# Sheet.net
KiCad netlist of a schematic drawn in Altium Designer
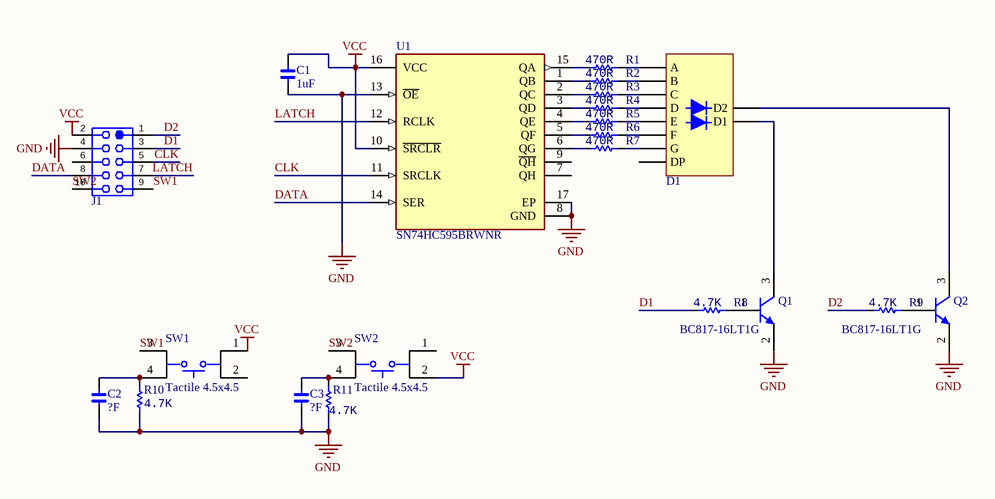
[diagram p0: Sheet.SchDoc]

(export (version "E")
  (design (tool "Eeschema 10.0.6"))
  (components
    (comp (ref "C1")
      (value "1uF")
      (footprint "C0603C-IPC_B")
      (description "0603 Multilayer Ceramic Capacitors MLCC - SMD/SMT ROHS")
      (libsource (lib "MAT_Component_Support") (part "Cap_0603"))
    )
    (comp (ref "C2")
      (value "?F")
      (footprint "C0603C-IPC_B")
      (description "0603 Multilayer Ceramic Capacitors MLCC - SMD/SMT ROHS")
      (libsource (lib "MAT_Component_Support") (part "Cap_0603"))
    )
    (comp (ref "C3")
      (value "?F")
      (footprint "C0603C-IPC_B")
      (description "0603 Multilayer Ceramic Capacitors MLCC - SMD/SMT ROHS")
      (libsource (lib "MAT_Component_Support") (part "Cap_0603"))
    )
    (comp (ref "D1")
      (value "7SEG_028_DUAL_CC")
      (footprint "7seg_2digit_028inch")
      (description "Common-Cathode (CC)")
      (libsource (lib "MAT_Component_Support") (part "2821AS"))
    )
    (comp (ref "J1")
      (value "HDRM_2x5_127_90")
      (footprint "HDRM_2x05J_90")
      (libsource (lib "MAT_Component_Support") (part "HDRM_2x5_127_90"))
    )
    (comp (ref "Q1")
      (value "BC817-16LT1G")
      (footprint "ONSC-SOT-23-3-318-08_V")
      (description "General Purpose Transistor, NPN Silicon, 3-Pin SOT-23, Pb-Free, Tape and Reel")
      (fields (field (name "MANUFACTURER") "On Semiconductor"))
      (libsource (lib "Altium Content Vault") (part "ONSC-NPN-B1E2C3-3"))
    )
    (comp (ref "Q2")
      (value "BC817-16LT1G")
      (footprint "ONSC-SOT-23-3-318-08_V")
      (description "General Purpose Transistor, NPN Silicon, 3-Pin SOT-23, Pb-Free, Tape and Reel")
      (fields (field (name "MANUFACTURER") "On Semiconductor"))
      (libsource (lib "Altium Content Vault") (part "ONSC-NPN-B1E2C3-3"))
    )
    (comp (ref "R1")
      (value "RC-0603")
      (footprint "RC0603-IPC_B")
      (description "±1% 0603 Chip Resistor - Surface Mount ROHS")
      (fields (field (name "TOLERANCE") "±1%") (field (name "RESISTANCE") "470R"))
      (libsource (lib "[MAT]_Resistors") (part "RC-0603"))
    )
    (comp (ref "R2")
      (value "RC-0603")
      (footprint "RC0603-IPC_B")
      (description "±1% 0603 Chip Resistor - Surface Mount ROHS")
      (fields (field (name "TOLERANCE") "±1%") (field (name "RESISTANCE") "470R"))
      (libsource (lib "[MAT]_Resistors") (part "RC-0603"))
    )
    (comp (ref "R3")
      (value "RC-0603")
      (footprint "RC0603-IPC_B")
      (description "±1% 0603 Chip Resistor - Surface Mount ROHS")
      (fields (field (name "TOLERANCE") "±1%") (field (name "RESISTANCE") "470R"))
      (libsource (lib "[MAT]_Resistors") (part "RC-0603"))
    )
    (comp (ref "R4")
      (value "RC-0603")
      (footprint "RC0603-IPC_B")
      (description "±1% 0603 Chip Resistor - Surface Mount ROHS")
      (fields (field (name "TOLERANCE") "±1%") (field (name "RESISTANCE") "470R"))
      (libsource (lib "[MAT]_Resistors") (part "RC-0603"))
    )
    (comp (ref "R5")
      (value "RC-0603")
      (footprint "RC0603-IPC_B")
      (description "±1% 0603 Chip Resistor - Surface Mount ROHS")
      (fields (field (name "TOLERANCE") "±1%") (field (name "RESISTANCE") "470R"))
      (libsource (lib "[MAT]_Resistors") (part "RC-0603"))
    )
    (comp (ref "R6")
      (value "RC-0603")
      (footprint "RC0603-IPC_B")
      (description "±1% 0603 Chip Resistor - Surface Mount ROHS")
      (fields (field (name "TOLERANCE") "±1%") (field (name "RESISTANCE") "470R"))
      (libsource (lib "[MAT]_Resistors") (part "RC-0603"))
    )
    (comp (ref "R7")
      (value "RC-0603")
      (footprint "RC0603-IPC_B")
      (description "±1% 0603 Chip Resistor - Surface Mount ROHS")
      (fields (field (name "TOLERANCE") "±1%") (field (name "RESISTANCE") "470R"))
      (libsource (lib "[MAT]_Resistors") (part "RC-0603"))
    )
    (comp (ref "R8")
      (value "RC-0603")
      (footprint "RC0603-IPC_B")
      (description "±1% 0603 Chip Resistor - Surface Mount ROHS")
      (fields (field (name "TOLERANCE") "±1%") (field (name "RESISTANCE") "4.7K"))
      (libsource (lib "[MAT]_Resistors") (part "RC-0603"))
    )
    (comp (ref "R9")
      (value "RC-0603")
      (footprint "RC0603-IPC_B")
      (description "±1% 0603 Chip Resistor - Surface Mount ROHS")
      (fields (field (name "TOLERANCE") "±1%") (field (name "RESISTANCE") "4.7K"))
      (libsource (lib "[MAT]_Resistors") (part "RC-0603"))
    )
    (comp (ref "R10")
      (value "RC-0603")
      (footprint "RC0603-IPC_B")
      (description "±1% 0603 Chip Resistor - Surface Mount ROHS")
      (fields (field (name "TOLERANCE") "±1%") (field (name "RESISTANCE") "4.7K"))
      (libsource (lib "[MAT]_Resistors") (part "RC-0603"))
    )
    (comp (ref "R11")
      (value "RC-0603")
      (footprint "RC0603-IPC_B")
      (description "±1% 0603 Chip Resistor - Surface Mount ROHS")
      (fields (field (name "TOLERANCE") "±1%") (field (name "RESISTANCE") "4.7K"))
      (libsource (lib "[MAT]_Resistors") (part "RC-0603"))
    )
    (comp (ref "SW1")
      (value "Tactile 4.5x4.5")
      (footprint "Tactile_45x45_SMD")
      (description "SWITCH TACTILE SPST-NO 50MA 12V")
      (libsource (lib "[MAT]_Switches") (part "Tactile 4.5x4.5"))
    )
    (comp (ref "SW2")
      (value "Tactile 4.5x4.5")
      (footprint "Tactile_45x45_SMD")
      (description "SWITCH TACTILE SPST-NO 50MA 12V")
      (libsource (lib "[MAT]_Switches") (part "Tactile 4.5x4.5"))
    )
    (comp (ref "U1")
      (value "SN74HC595BRWNR")
      (footprint "FP-RWN0016A-MFG")
      (description "IC SHIFT REGISTER 8BIT 16X1QFN")
      (libsource (lib "Altium Content Vault") (part "b6d3b81886be85189d97a3b732217c7"))
    )
  )
  (nets
    (net (code "1") (name "/CLK") (class "Default")
      (node (ref "J1") (pin "5") (pinfunction "5_5") (pintype "passive"))
      (node (ref "U1") (pin "11") (pinfunction "SRCLK_11") (pintype "input"))
    )
    (net (code "2") (name "/D1") (class "Default")
      (node (ref "J1") (pin "3") (pinfunction "3_3") (pintype "passive"))
      (node (ref "R8") (pin "1") (pinfunction "1_1") (pintype "passive"))
    )
    (net (code "3") (name "/D2") (class "Default")
      (node (ref "J1") (pin "1") (pinfunction "1_1") (pintype "passive"))
      (node (ref "R9") (pin "1") (pinfunction "1_1") (pintype "passive"))
    )
    (net (code "4") (name "/DATA") (class "Default")
      (node (ref "J1") (pin "8") (pinfunction "8_8") (pintype "passive"))
      (node (ref "U1") (pin "14") (pinfunction "SER_14") (pintype "input"))
    )
    (net (code "5") (name "/LATCH") (class "Default")
      (node (ref "J1") (pin "7") (pinfunction "7_7") (pintype "passive"))
      (node (ref "U1") (pin "12") (pinfunction "RCLK_12") (pintype "input"))
    )
    (net (code "6") (name "/SW1") (class "Default")
      (node (ref "J1") (pin "9") (pinfunction "9_9") (pintype "passive"))
      (node (ref "SW1") (pin "3") (pinfunction "3_3") (pintype "passive"))
    )
    (net (code "7") (name "/SW2") (class "Default")
      (node (ref "J1") (pin "10") (pinfunction "10_10") (pintype "passive"))
      (node (ref "SW2") (pin "3") (pinfunction "3_3") (pintype "passive"))
    )
    (net (code "8") (name "GND") (class "Default")
      (node (ref "C1") (pin "1") (pinfunction "1_1") (pintype "passive"))
      (node (ref "C2") (pin "1") (pinfunction "1_1") (pintype "passive"))
      (node (ref "C3") (pin "1") (pinfunction "1_1") (pintype "passive"))
      (node (ref "J1") (pin "4") (pinfunction "4_4") (pintype "passive"))
      (node (ref "Q1") (pin "2") (pinfunction "E_2") (pintype "passive"))
      (node (ref "Q2") (pin "2") (pinfunction "E_2") (pintype "passive"))
      (node (ref "R10") (pin "1") (pinfunction "1_1") (pintype "passive"))
      (node (ref "R11") (pin "1") (pinfunction "1_1") (pintype "passive"))
      (node (ref "U1") (pin "13") (pinfunction "~{OE}_13") (pintype "input"))
      (node (ref "U1") (pin "17") (pinfunction "EP_17") (pintype "power_in"))
      (node (ref "U1") (pin "8") (pinfunction "GND_8") (pintype "power_in"))
    )
    (net (code "9") (name "Net-(C2-Pad2)") (class "Default")
      (node (ref "C2") (pin "2") (pinfunction "2_2") (pintype "passive"))
      (node (ref "R10") (pin "2") (pinfunction "2_2") (pintype "passive"))
      (node (ref "SW1") (pin "4") (pinfunction "4_4") (pintype "passive"))
    )
    (net (code "10") (name "Net-(C3-Pad2)") (class "Default")
      (node (ref "C3") (pin "2") (pinfunction "2_2") (pintype "passive"))
      (node (ref "R11") (pin "2") (pinfunction "2_2") (pintype "passive"))
      (node (ref "SW2") (pin "4") (pinfunction "4_4") (pintype "passive"))
    )
    (net (code "11") (name "Net-(D1-A)") (class "Default")
      (node (ref "D1") (pin "7") (pinfunction "A_7") (pintype "passive"))
      (node (ref "R1") (pin "2") (pinfunction "2_2") (pintype "passive"))
    )
    (net (code "12") (name "Net-(D1-B)") (class "Default")
      (node (ref "D1") (pin "8") (pinfunction "B_8") (pintype "passive"))
      (node (ref "R2") (pin "2") (pinfunction "2_2") (pintype "passive"))
    )
    (net (code "13") (name "Net-(D1-C)") (class "Default")
      (node (ref "D1") (pin "3") (pinfunction "C_3") (pintype "passive"))
      (node (ref "R3") (pin "2") (pinfunction "2_2") (pintype "passive"))
    )
    (net (code "14") (name "Net-(D1-D)") (class "Default")
      (node (ref "D1") (pin "2") (pinfunction "D_2") (pintype "passive"))
      (node (ref "R4") (pin "2") (pinfunction "2_2") (pintype "passive"))
    )
    (net (code "15") (name "Net-(D1-D1)") (class "Default")
      (node (ref "D1") (pin "9") (pinfunction "D1_9") (pintype "passive"))
      (node (ref "Q1") (pin "3") (pinfunction "C_3") (pintype "passive"))
    )
    (net (code "16") (name "Net-(D1-D2)") (class "Default")
      (node (ref "D1") (pin "6") (pinfunction "D2_6") (pintype "passive"))
      (node (ref "Q2") (pin "3") (pinfunction "C_3") (pintype "passive"))
    )
    (net (code "17") (name "Net-(D1-E)") (class "Default")
      (node (ref "D1") (pin "1") (pinfunction "E_1") (pintype "passive"))
      (node (ref "R5") (pin "2") (pinfunction "2_2") (pintype "passive"))
    )
    (net (code "18") (name "Net-(D1-F)") (class "Default")
      (node (ref "D1") (pin "10") (pinfunction "F_10") (pintype "passive"))
      (node (ref "R6") (pin "2") (pinfunction "2_2") (pintype "passive"))
    )
    (net (code "19") (name "Net-(D1-G)") (class "Default")
      (node (ref "D1") (pin "4") (pinfunction "G_4") (pintype "passive"))
      (node (ref "R7") (pin "2") (pinfunction "2_2") (pintype "passive"))
    )
    (net (code "20") (name "Net-(Q1-B)") (class "Default")
      (node (ref "Q1") (pin "1") (pinfunction "B_1") (pintype "passive"))
      (node (ref "R8") (pin "2") (pinfunction "2_2") (pintype "passive"))
    )
    (net (code "21") (name "Net-(Q2-B)") (class "Default")
      (node (ref "Q2") (pin "1") (pinfunction "B_1") (pintype "passive"))
      (node (ref "R9") (pin "2") (pinfunction "2_2") (pintype "passive"))
    )
    (net (code "22") (name "Net-(U1-QA)") (class "Default")
      (node (ref "R1") (pin "1") (pinfunction "1_1") (pintype "passive"))
      (node (ref "U1") (pin "15") (pinfunction "QA_15") (pintype "output"))
    )
    (net (code "23") (name "Net-(U1-QB)") (class "Default")
      (node (ref "R2") (pin "1") (pinfunction "1_1") (pintype "passive"))
      (node (ref "U1") (pin "1") (pinfunction "QB_1") (pintype "tri_state"))
    )
    (net (code "24") (name "Net-(U1-QC)") (class "Default")
      (node (ref "R3") (pin "1") (pinfunction "1_1") (pintype "passive"))
      (node (ref "U1") (pin "2") (pinfunction "QC_2") (pintype "tri_state"))
    )
    (net (code "25") (name "Net-(U1-QD)") (class "Default")
      (node (ref "R4") (pin "1") (pinfunction "1_1") (pintype "passive"))
      (node (ref "U1") (pin "3") (pinfunction "QD_3") (pintype "tri_state"))
    )
    (net (code "26") (name "Net-(U1-QE)") (class "Default")
      (node (ref "R5") (pin "1") (pinfunction "1_1") (pintype "passive"))
      (node (ref "U1") (pin "4") (pinfunction "QE_4") (pintype "tri_state"))
    )
    (net (code "27") (name "Net-(U1-QF)") (class "Default")
      (node (ref "R6") (pin "1") (pinfunction "1_1") (pintype "passive"))
      (node (ref "U1") (pin "5") (pinfunction "QF_5") (pintype "tri_state"))
    )
    (net (code "28") (name "Net-(U1-QG)") (class "Default")
      (node (ref "R7") (pin "1") (pinfunction "1_1") (pintype "passive"))
      (node (ref "U1") (pin "6") (pinfunction "QG_6") (pintype "tri_state"))
    )
    (net (code "29") (name "VCC") (class "Default")
      (node (ref "C1") (pin "2") (pinfunction "2_2") (pintype "passive"))
      (node (ref "J1") (pin "2") (pinfunction "2_2") (pintype "passive"))
      (node (ref "SW1") (pin "1") (pinfunction "1_1") (pintype "passive"))
      (node (ref "SW2") (pin "2") (pinfunction "2_2") (pintype "passive"))
      (node (ref "U1") (pin "10") (pinfunction "~{SRCLR}_10") (pintype "input"))
      (node (ref "U1") (pin "16") (pinfunction "VCC_16") (pintype "power_in"))
    )
    (net (code "30") (name "unconnected-(D1-DP-Pad5)") (class "Default")
      (node (ref "D1") (pin "5") (pinfunction "DP_5") (pintype "passive"))
    )
    (net (code "31") (name "unconnected-(J1-Pad6)") (class "Default")
      (node (ref "J1") (pin "6") (pinfunction "6_6") (pintype "passive"))
    )
    (net (code "32") (name "unconnected-(SW1-Pad2)") (class "Default")
      (node (ref "SW1") (pin "2") (pinfunction "2_2") (pintype "passive"))
    )
    (net (code "33") (name "unconnected-(SW2-Pad1)") (class "Default")
      (node (ref "SW2") (pin "1") (pinfunction "1_1") (pintype "passive"))
    )
    (net (code "34") (name "unconnected-(U1-QH-Pad7)") (class "Default")
      (node (ref "U1") (pin "7") (pinfunction "QH_7") (pintype "tri_state"))
    )
    (net (code "35") (name "unconnected-(U1-~{QH}-Pad9)") (class "Default")
      (node (ref "U1") (pin "9") (pinfunction "~{QH}_9") (pintype "tri_state"))
    )
  )
)
